# Senior_Project_Board_v2.net
KiCad netlist of a schematic drawn in EAGLE
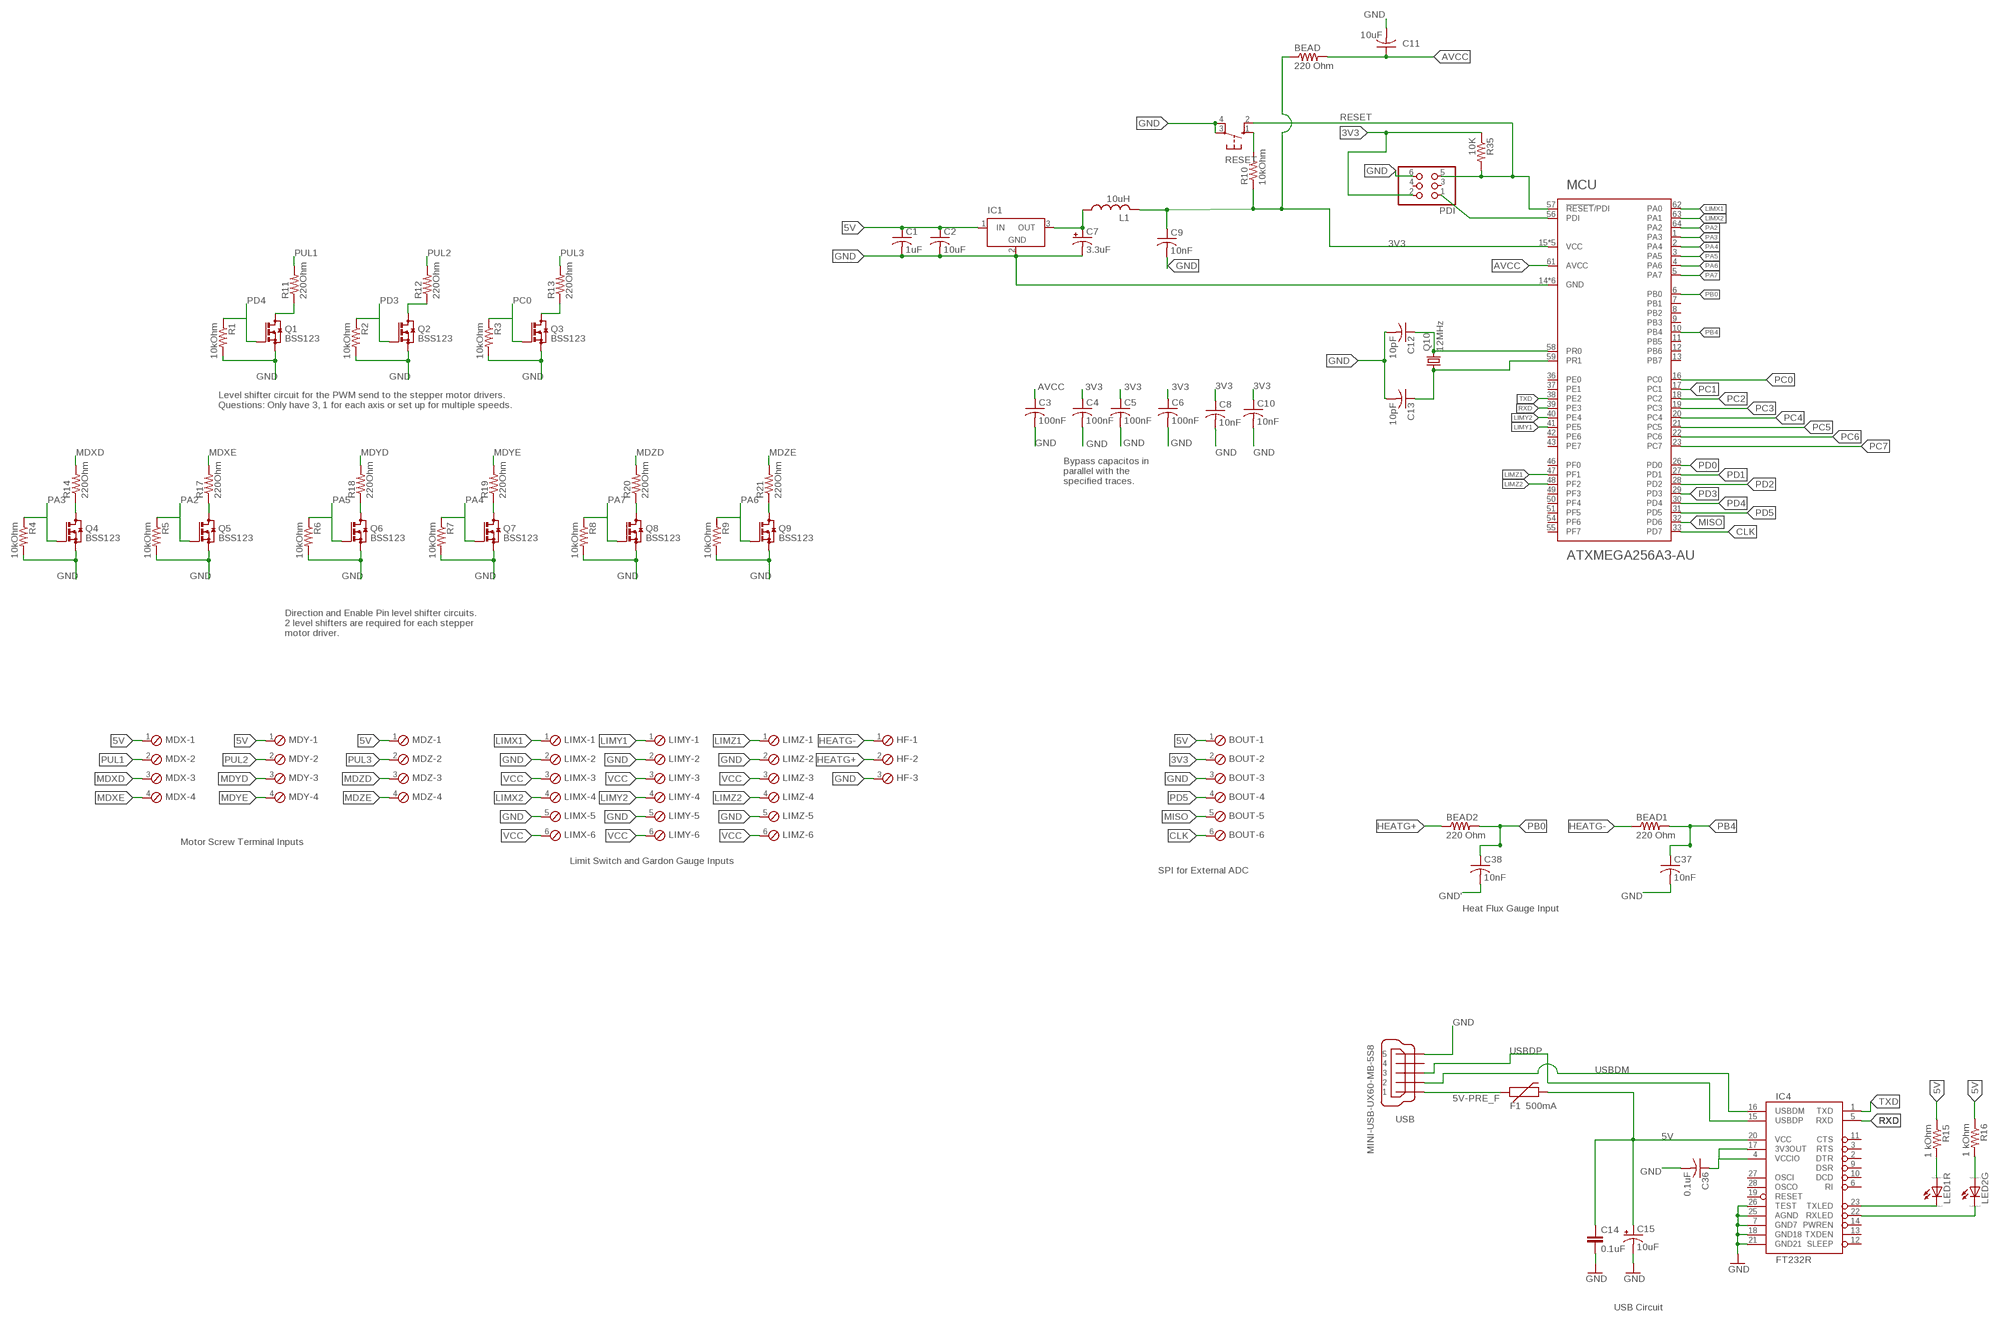
[diagram p0: schematic, sheet 1, part 1 of 3]
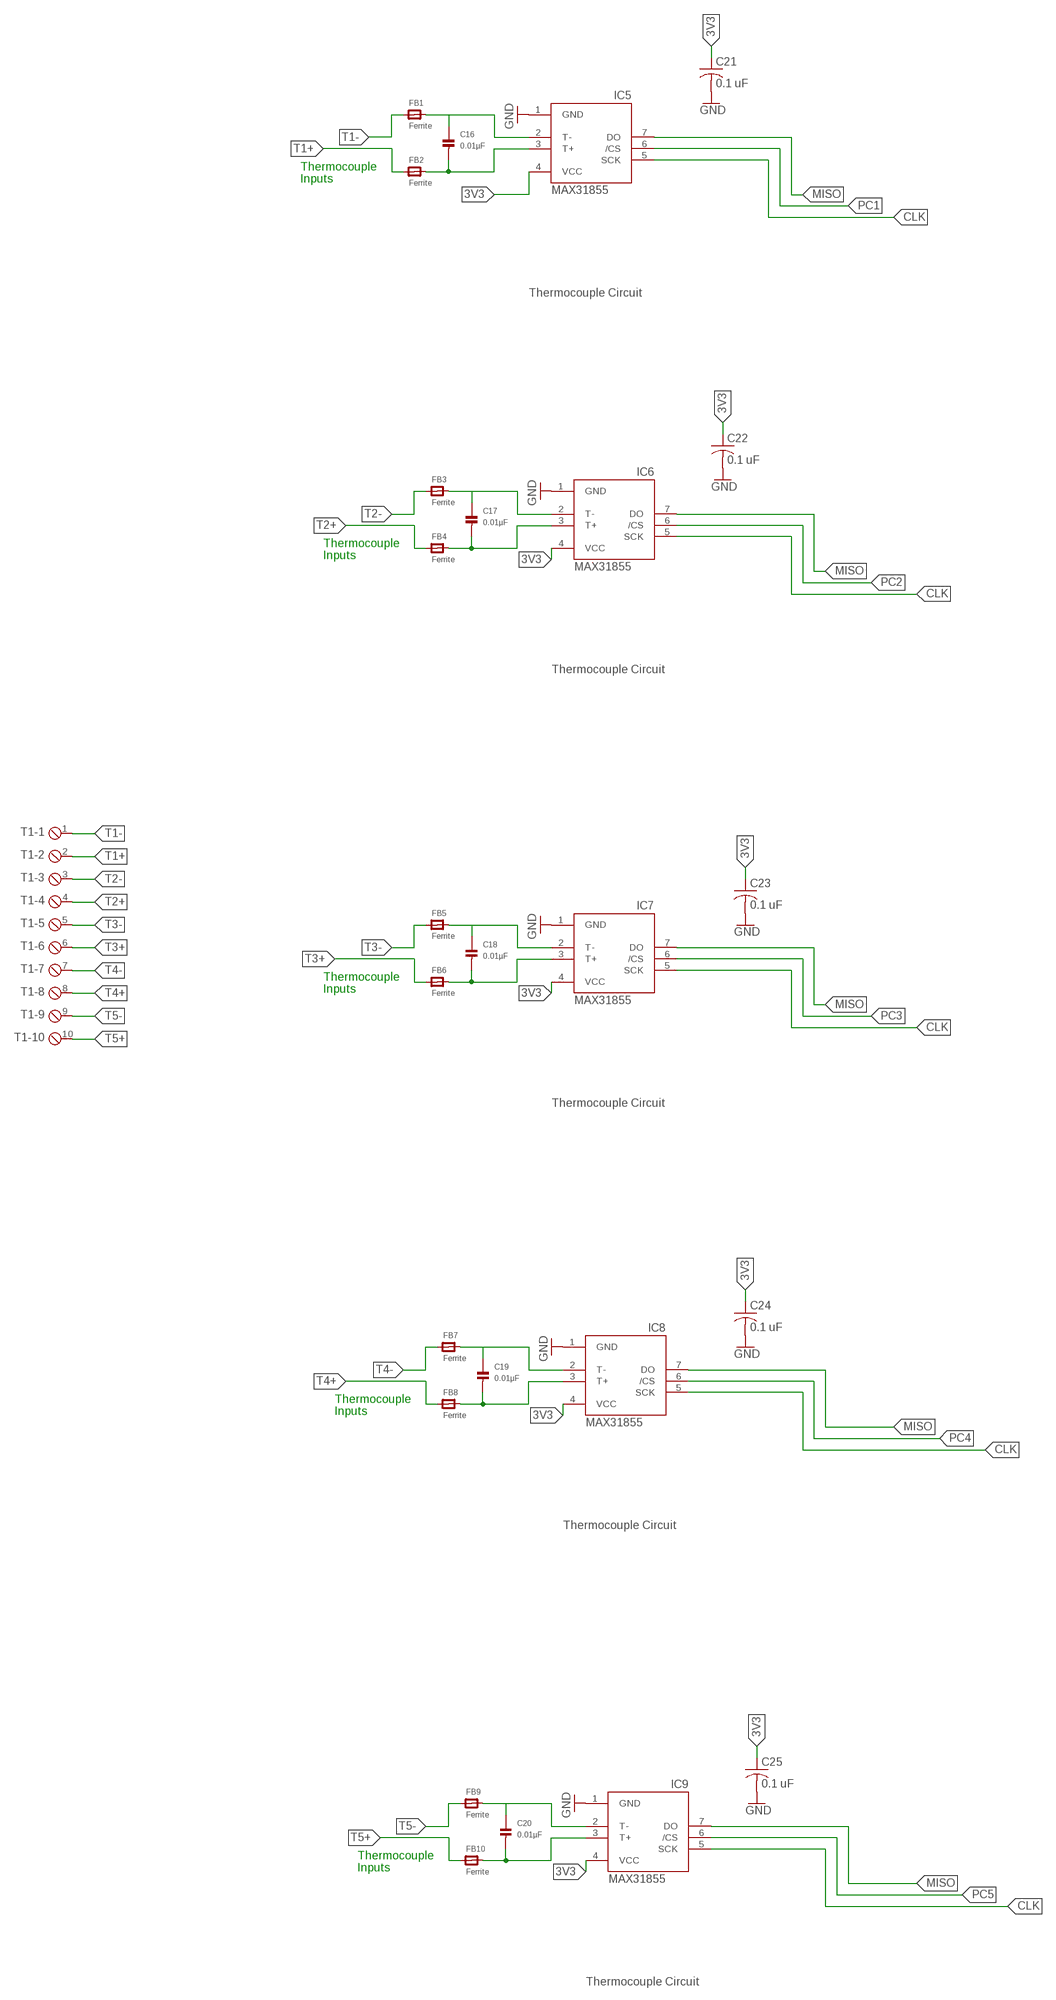
[diagram p1: schematic, sheet 1, part 2 of 3]
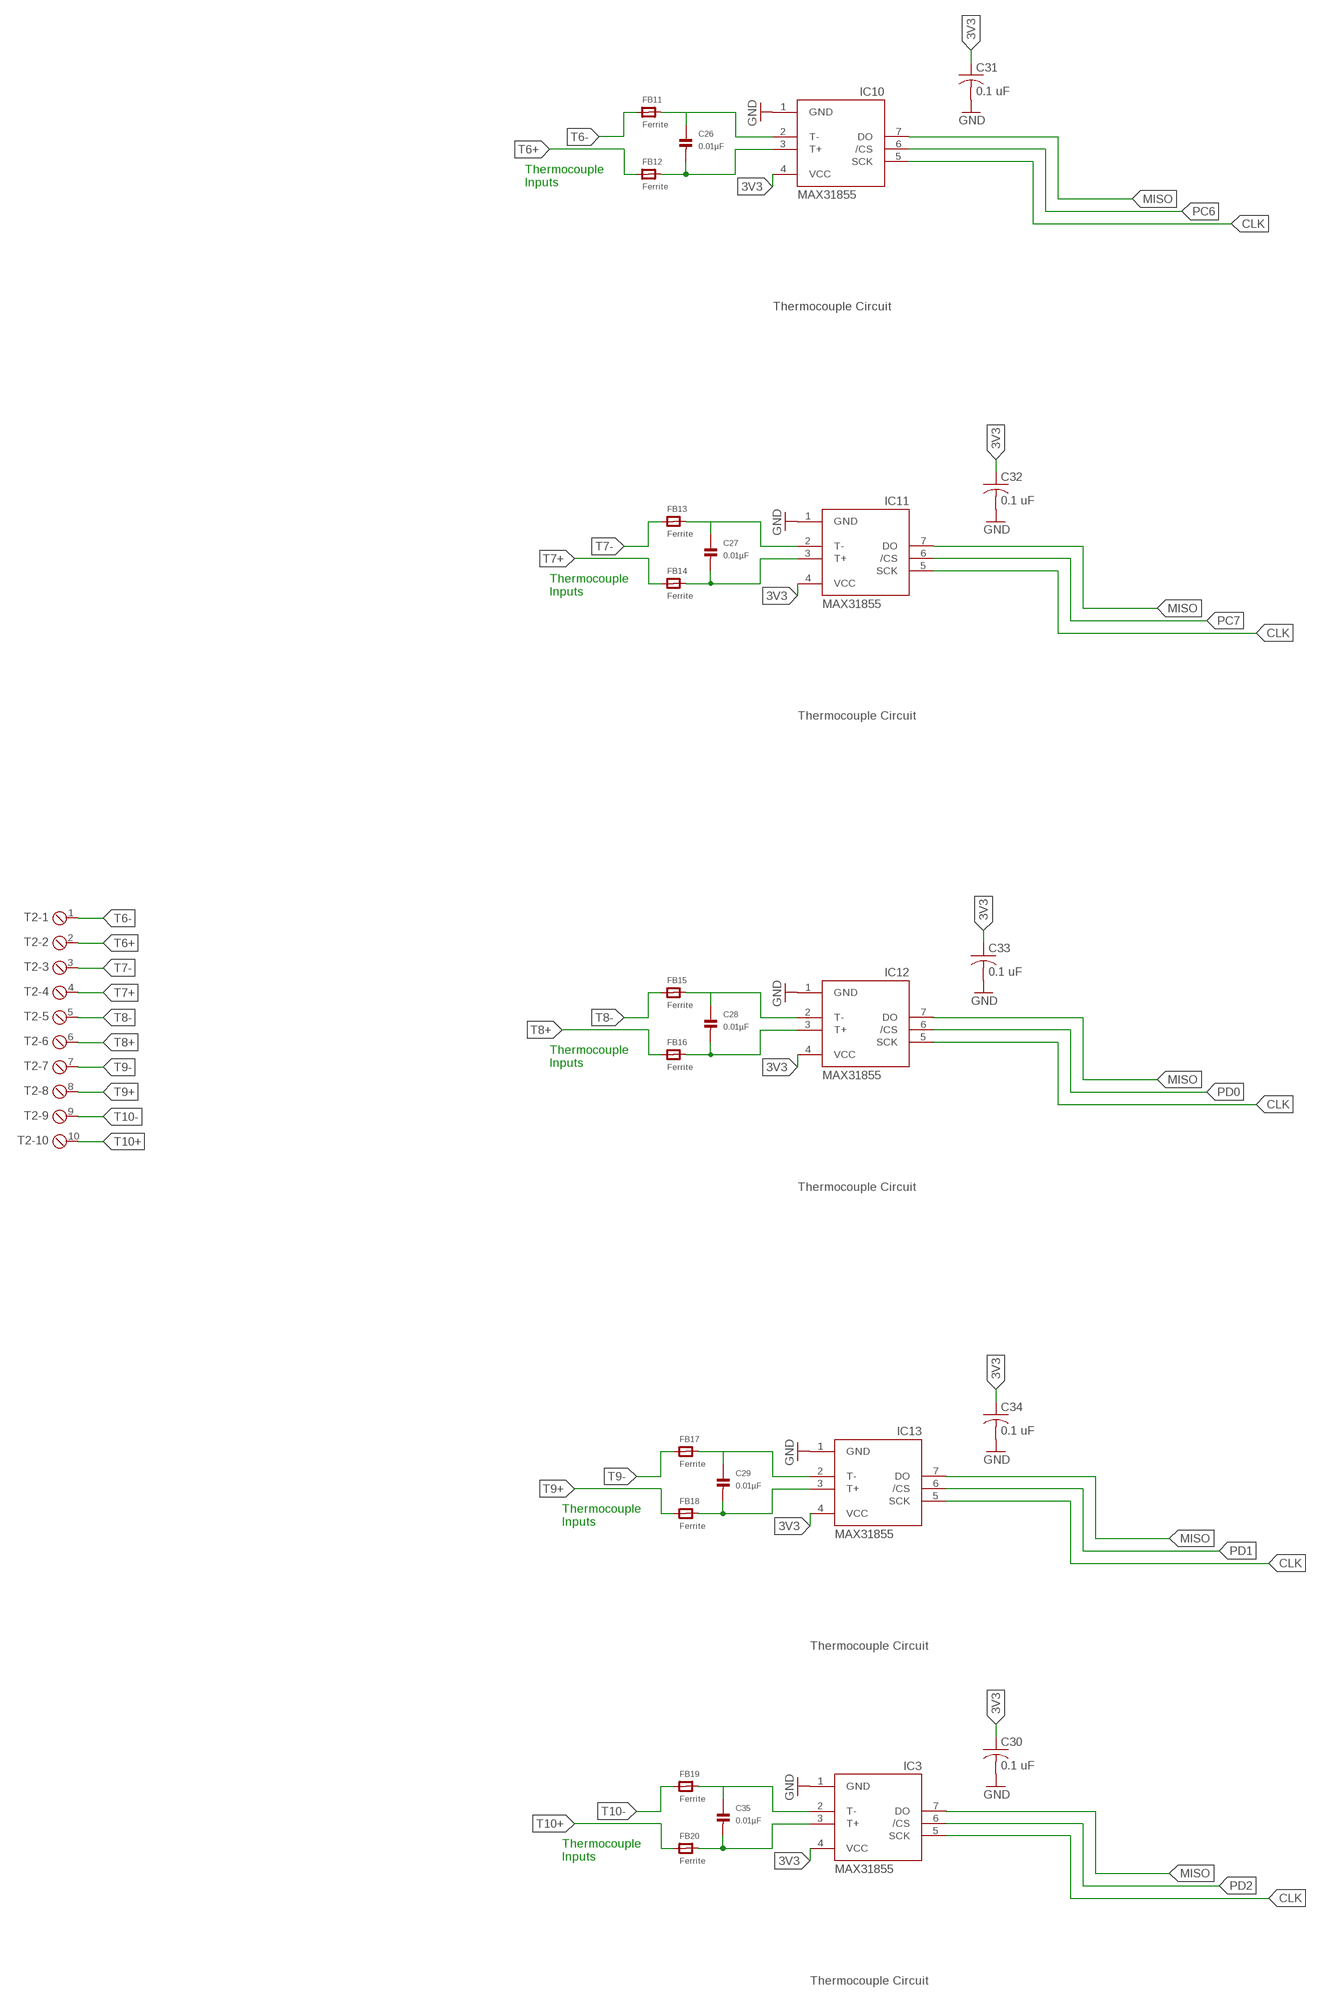
[diagram p2: schematic, sheet 1, part 3 of 3]

(export (version "E")
  (design (tool "Eeschema 10.0.6"))
  (components
    (comp (ref "BEAD")
      (value "220 Ohm")
      (footprint "eagle-import:R0805")
      (libsource (lib "eagle-import") (part "rcl_R-US_R0805"))
    )
    (comp (ref "BEAD1")
      (value "220 Ohm")
      (footprint "eagle-import:R0805")
      (libsource (lib "eagle-import") (part "rcl_R-US_R0805"))
    )
    (comp (ref "BEAD2")
      (value "220 Ohm")
      (footprint "eagle-import:R0805")
      (libsource (lib "eagle-import") (part "rcl_R-US_R0805"))
    )
    (comp (ref "BOUT")
      (value "MPT6")
      (footprint "eagle-import:6POL254")
      (libsource (lib "eagle-import") (part "MPT6"))
    )
    (comp (ref "C1")
      (value "1uF")
      (footprint "eagle-import:C0805")
      (libsource (lib "eagle-import") (part "rcl_C-USC0805"))
    )
    (comp (ref "C2")
      (value "10uF")
      (footprint "eagle-import:C0805")
      (libsource (lib "eagle-import") (part "rcl_C-USC0805"))
    )
    (comp (ref "C3")
      (value "100nF")
      (footprint "eagle-import:C0805")
      (libsource (lib "eagle-import") (part "rcl_C-USC0805"))
    )
    (comp (ref "C4")
      (value "100nF")
      (footprint "eagle-import:C0805")
      (libsource (lib "eagle-import") (part "rcl_C-USC0805"))
    )
    (comp (ref "C5")
      (value "100nF")
      (footprint "eagle-import:C0805")
      (libsource (lib "eagle-import") (part "rcl_C-USC0805"))
    )
    (comp (ref "C6")
      (value "100nF")
      (footprint "eagle-import:C0805")
      (libsource (lib "eagle-import") (part "rcl_C-USC0805"))
    )
    (comp (ref "C7")
      (value "3.3uF")
      (footprint "eagle-import:CT3216")
      (libsource (lib "eagle-import") (part "CPOL-USCT3216"))
    )
    (comp (ref "C8")
      (value "10nF")
      (footprint "eagle-import:C0805")
      (libsource (lib "eagle-import") (part "rcl_C-USC0805"))
    )
    (comp (ref "C9")
      (value "10nF")
      (footprint "eagle-import:C0805")
      (libsource (lib "eagle-import") (part "rcl_C-USC0805"))
    )
    (comp (ref "C10")
      (value "10nF")
      (footprint "eagle-import:C0805")
      (libsource (lib "eagle-import") (part "rcl_C-USC0805"))
    )
    (comp (ref "C11")
      (value "10uF")
      (footprint "eagle-import:C0805")
      (libsource (lib "eagle-import") (part "rcl_C-USC0805"))
    )
    (comp (ref "C12")
      (value "10pF")
      (footprint "eagle-import:C0805")
      (libsource (lib "eagle-import") (part "rcl_C-USC0805"))
    )
    (comp (ref "C13")
      (value "10pF")
      (footprint "eagle-import:C0805")
      (libsource (lib "eagle-import") (part "rcl_C-USC0805"))
    )
    (comp (ref "C14")
      (value "0.1uF")
      (footprint "eagle-import:0603-CAP")
      (libsource (lib "eagle-import") (part "0.1UF-25V(+80/-20%)(0603)"))
    )
    (comp (ref "C15")
      (value "10uF")
      (footprint "eagle-import:EIA3216")
      (libsource (lib "eagle-import") (part "10UF-16V-10%(TANT)"))
    )
    (comp (ref "C16")
      (value "0.01µF")
      (footprint "eagle-import:_0805")
      (libsource (lib "eagle-import") (part "CAP_CERAMIC_0805"))
    )
    (comp (ref "C17")
      (value "0.01µF")
      (footprint "eagle-import:_0805")
      (libsource (lib "eagle-import") (part "CAP_CERAMIC_0805"))
    )
    (comp (ref "C18")
      (value "0.01µF")
      (footprint "eagle-import:_0805")
      (libsource (lib "eagle-import") (part "CAP_CERAMIC_0805"))
    )
    (comp (ref "C19")
      (value "0.01µF")
      (footprint "eagle-import:_0805")
      (libsource (lib "eagle-import") (part "CAP_CERAMIC_0805"))
    )
    (comp (ref "C20")
      (value "0.01µF")
      (footprint "eagle-import:_0805")
      (libsource (lib "eagle-import") (part "CAP_CERAMIC_0805"))
    )
    (comp (ref "C21")
      (value "0.1 uF")
      (footprint "eagle-import:C0805K")
      (libsource (lib "eagle-import") (part "C-USC0805K"))
    )
    (comp (ref "C22")
      (value "0.1 uF")
      (footprint "eagle-import:C0805K")
      (libsource (lib "eagle-import") (part "C-USC0805K"))
    )
    (comp (ref "C23")
      (value "0.1 uF")
      (footprint "eagle-import:C0805K")
      (libsource (lib "eagle-import") (part "C-USC0805K"))
    )
    (comp (ref "C24")
      (value "0.1 uF")
      (footprint "eagle-import:C0805K")
      (libsource (lib "eagle-import") (part "C-USC0805K"))
    )
    (comp (ref "C25")
      (value "0.1 uF")
      (footprint "eagle-import:C0805K")
      (libsource (lib "eagle-import") (part "C-USC0805K"))
    )
    (comp (ref "C26")
      (value "0.01µF")
      (footprint "eagle-import:_0805")
      (libsource (lib "eagle-import") (part "CAP_CERAMIC_0805"))
    )
    (comp (ref "C27")
      (value "0.01µF")
      (footprint "eagle-import:_0805")
      (libsource (lib "eagle-import") (part "CAP_CERAMIC_0805"))
    )
    (comp (ref "C28")
      (value "0.01µF")
      (footprint "eagle-import:_0805")
      (libsource (lib "eagle-import") (part "CAP_CERAMIC_0805"))
    )
    (comp (ref "C29")
      (value "0.01µF")
      (footprint "eagle-import:_0805")
      (libsource (lib "eagle-import") (part "CAP_CERAMIC_0805"))
    )
    (comp (ref "C30")
      (value "0.1 uF")
      (footprint "eagle-import:C0805K")
      (libsource (lib "eagle-import") (part "C-USC0805K"))
    )
    (comp (ref "C31")
      (value "0.1 uF")
      (footprint "eagle-import:C0805K")
      (libsource (lib "eagle-import") (part "C-USC0805K"))
    )
    (comp (ref "C32")
      (value "0.1 uF")
      (footprint "eagle-import:C0805K")
      (libsource (lib "eagle-import") (part "C-USC0805K"))
    )
    (comp (ref "C33")
      (value "0.1 uF")
      (footprint "eagle-import:C0805K")
      (libsource (lib "eagle-import") (part "C-USC0805K"))
    )
    (comp (ref "C34")
      (value "0.1 uF")
      (footprint "eagle-import:C0805K")
      (libsource (lib "eagle-import") (part "C-USC0805K"))
    )
    (comp (ref "C35")
      (value "0.01µF")
      (footprint "eagle-import:_0805")
      (libsource (lib "eagle-import") (part "CAP_CERAMIC_0805"))
    )
    (comp (ref "C36")
      (value "0.1uF")
      (footprint "eagle-import:C0805")
      (libsource (lib "eagle-import") (part "rcl_C-USC0805"))
    )
    (comp (ref "C37")
      (value "10nF")
      (footprint "eagle-import:C0805")
      (libsource (lib "eagle-import") (part "rcl_C-USC0805"))
    )
    (comp (ref "C38")
      (value "10nF")
      (footprint "eagle-import:C0805")
      (libsource (lib "eagle-import") (part "rcl_C-USC0805"))
    )
    (comp (ref "F1")
      (value "500mA")
      (footprint "eagle-import:PTC-1206")
      (libsource (lib "eagle-import") (part "PTCSMD"))
    )
    (comp (ref "FB1")
      (value "Ferrite")
      (footprint "eagle-import:_0805")
      (libsource (lib "eagle-import") (part "FERRITE_0805"))
    )
    (comp (ref "FB2")
      (value "Ferrite")
      (footprint "eagle-import:_0805")
      (libsource (lib "eagle-import") (part "FERRITE_0805"))
    )
    (comp (ref "FB3")
      (value "Ferrite")
      (footprint "eagle-import:_0805")
      (libsource (lib "eagle-import") (part "FERRITE_0805"))
    )
    (comp (ref "FB4")
      (value "Ferrite")
      (footprint "eagle-import:_0805")
      (libsource (lib "eagle-import") (part "FERRITE_0805"))
    )
    (comp (ref "FB5")
      (value "Ferrite")
      (footprint "eagle-import:_0805")
      (libsource (lib "eagle-import") (part "FERRITE_0805"))
    )
    (comp (ref "FB6")
      (value "Ferrite")
      (footprint "eagle-import:_0805")
      (libsource (lib "eagle-import") (part "FERRITE_0805"))
    )
    (comp (ref "FB7")
      (value "Ferrite")
      (footprint "eagle-import:_0805")
      (libsource (lib "eagle-import") (part "FERRITE_0805"))
    )
    (comp (ref "FB8")
      (value "Ferrite")
      (footprint "eagle-import:_0805")
      (libsource (lib "eagle-import") (part "FERRITE_0805"))
    )
    (comp (ref "FB9")
      (value "Ferrite")
      (footprint "eagle-import:_0805")
      (libsource (lib "eagle-import") (part "FERRITE_0805"))
    )
    (comp (ref "FB10")
      (value "Ferrite")
      (footprint "eagle-import:_0805")
      (libsource (lib "eagle-import") (part "FERRITE_0805"))
    )
    (comp (ref "FB11")
      (value "Ferrite")
      (footprint "eagle-import:_0805")
      (libsource (lib "eagle-import") (part "FERRITE_0805"))
    )
    (comp (ref "FB12")
      (value "Ferrite")
      (footprint "eagle-import:_0805")
      (libsource (lib "eagle-import") (part "FERRITE_0805"))
    )
    (comp (ref "FB13")
      (value "Ferrite")
      (footprint "eagle-import:_0805")
      (libsource (lib "eagle-import") (part "FERRITE_0805"))
    )
    (comp (ref "FB14")
      (value "Ferrite")
      (footprint "eagle-import:_0805")
      (libsource (lib "eagle-import") (part "FERRITE_0805"))
    )
    (comp (ref "FB15")
      (value "Ferrite")
      (footprint "eagle-import:_0805")
      (libsource (lib "eagle-import") (part "FERRITE_0805"))
    )
    (comp (ref "FB16")
      (value "Ferrite")
      (footprint "eagle-import:_0805")
      (libsource (lib "eagle-import") (part "FERRITE_0805"))
    )
    (comp (ref "FB17")
      (value "Ferrite")
      (footprint "eagle-import:_0805")
      (libsource (lib "eagle-import") (part "FERRITE_0805"))
    )
    (comp (ref "FB18")
      (value "Ferrite")
      (footprint "eagle-import:_0805")
      (libsource (lib "eagle-import") (part "FERRITE_0805"))
    )
    (comp (ref "FB19")
      (value "Ferrite")
      (footprint "eagle-import:_0805")
      (libsource (lib "eagle-import") (part "FERRITE_0805"))
    )
    (comp (ref "FB20")
      (value "Ferrite")
      (footprint "eagle-import:_0805")
      (libsource (lib "eagle-import") (part "FERRITE_0805"))
    )
    (comp (ref "HF")
      (value "MPT3")
      (footprint "eagle-import:3POL254")
      (libsource (lib "eagle-import") (part "MPT3"))
    )
    (comp (ref "IC1")
      (value "LT1129CST5")
      (footprint "eagle-import:SOT223")
      (fields (field (name "MPN") "LT1129CST-5#PBF"))
      (libsource (lib "eagle-import") (part "LT1129CST5"))
    )
    (comp (ref "IC3")
      (value "MAX31855")
      (footprint "eagle-import:SO08")
      (libsource (lib "eagle-import") (part "MAX6675"))
    )
    (comp (ref "IC4")
      (value "FT232R")
      (footprint "eagle-import:SSOP28DB")
      (libsource (lib "eagle-import") (part "FT232RLSSOP"))
    )
    (comp (ref "IC5")
      (value "MAX31855")
      (footprint "eagle-import:SO08")
      (libsource (lib "eagle-import") (part "MAX6675"))
    )
    (comp (ref "IC6")
      (value "MAX31855")
      (footprint "eagle-import:SO08")
      (libsource (lib "eagle-import") (part "MAX6675"))
    )
    (comp (ref "IC7")
      (value "MAX31855")
      (footprint "eagle-import:SO08")
      (libsource (lib "eagle-import") (part "MAX6675"))
    )
    (comp (ref "IC8")
      (value "MAX31855")
      (footprint "eagle-import:SO08")
      (libsource (lib "eagle-import") (part "MAX6675"))
    )
    (comp (ref "IC9")
      (value "MAX31855")
      (footprint "eagle-import:SO08")
      (libsource (lib "eagle-import") (part "MAX6675"))
    )
    (comp (ref "IC10")
      (value "MAX31855")
      (footprint "eagle-import:SO08")
      (libsource (lib "eagle-import") (part "MAX6675"))
    )
    (comp (ref "IC11")
      (value "MAX31855")
      (footprint "eagle-import:SO08")
      (libsource (lib "eagle-import") (part "MAX6675"))
    )
    (comp (ref "IC12")
      (value "MAX31855")
      (footprint "eagle-import:SO08")
      (libsource (lib "eagle-import") (part "MAX6675"))
    )
    (comp (ref "IC13")
      (value "MAX31855")
      (footprint "eagle-import:SO08")
      (libsource (lib "eagle-import") (part "MAX6675"))
    )
    (comp (ref "L1")
      (value "10uH")
      (footprint "eagle-import:L1812")
      (libsource (lib "eagle-import") (part "L-USL1812"))
    )
    (comp (ref "LED1R")
      (value "LED_E")
      (footprint "eagle-import:LED_1206")
      (libsource (lib "eagle-import") (part "LED_E"))
    )
    (comp (ref "LED2G")
      (value "LED_E")
      (footprint "eagle-import:LED_1206")
      (libsource (lib "eagle-import") (part "LED_E"))
    )
    (comp (ref "LIMX")
      (value "MPT6")
      (footprint "eagle-import:6POL254")
      (libsource (lib "eagle-import") (part "MPT6"))
    )
    (comp (ref "LIMY")
      (value "MPT6")
      (footprint "eagle-import:6POL254")
      (libsource (lib "eagle-import") (part "MPT6"))
    )
    (comp (ref "LIMZ")
      (value "MPT6")
      (footprint "eagle-import:6POL254")
      (libsource (lib "eagle-import") (part "MPT6"))
    )
    (comp (ref "MCU")
      (value "ATXMEGA256A3-AU")
      (footprint "eagle-import:TQFP-64A-64")
      (libsource (lib "eagle-import") (part "ATXMEGA256A3-AU"))
    )
    (comp (ref "MDX")
      (value "MPT4")
      (footprint "eagle-import:4POL254")
      (libsource (lib "eagle-import") (part "MPT4"))
    )
    (comp (ref "MDY")
      (value "MPT4")
      (footprint "eagle-import:4POL254")
      (libsource (lib "eagle-import") (part "MPT4"))
    )
    (comp (ref "MDZ")
      (value "MPT4")
      (footprint "eagle-import:4POL254")
      (libsource (lib "eagle-import") (part "MPT4"))
    )
    (comp (ref "PDI")
      (value "PINHD-2X3")
      (footprint "eagle-import:2X03")
      (libsource (lib "eagle-import") (part "PINHD-2X3"))
    )
    (comp (ref "Q1")
      (value "BSS123")
      (footprint "eagle-import:SOT23")
      (libsource (lib "eagle-import") (part "BSS123"))
    )
    (comp (ref "Q2")
      (value "BSS123")
      (footprint "eagle-import:SOT23")
      (libsource (lib "eagle-import") (part "BSS123"))
    )
    (comp (ref "Q3")
      (value "BSS123")
      (footprint "eagle-import:SOT23")
      (libsource (lib "eagle-import") (part "BSS123"))
    )
    (comp (ref "Q4")
      (value "BSS123")
      (footprint "eagle-import:SOT23")
      (libsource (lib "eagle-import") (part "BSS123"))
    )
    (comp (ref "Q5")
      (value "BSS123")
      (footprint "eagle-import:SOT23")
      (libsource (lib "eagle-import") (part "BSS123"))
    )
    (comp (ref "Q6")
      (value "BSS123")
      (footprint "eagle-import:SOT23")
      (libsource (lib "eagle-import") (part "BSS123"))
    )
    (comp (ref "Q7")
      (value "BSS123")
      (footprint "eagle-import:SOT23")
      (libsource (lib "eagle-import") (part "BSS123"))
    )
    (comp (ref "Q8")
      (value "BSS123")
      (footprint "eagle-import:SOT23")
      (libsource (lib "eagle-import") (part "BSS123"))
    )
    (comp (ref "Q9")
      (value "BSS123")
      (footprint "eagle-import:SOT23")
      (libsource (lib "eagle-import") (part "BSS123"))
    )
    (comp (ref "Q10")
      (value "12MHz")
      (footprint "eagle-import:HC49_S")
      (libsource (lib "eagle-import") (part "CRYSTALHC49S"))
    )
    (comp (ref "R1")
      (value "10kOhm")
      (footprint "eagle-import:R0805")
      (libsource (lib "eagle-import") (part "rcl_R-US_R0805"))
    )
    (comp (ref "R2")
      (value "10kOhm")
      (footprint "eagle-import:R0805")
      (libsource (lib "eagle-import") (part "rcl_R-US_R0805"))
    )
    (comp (ref "R3")
      (value "10kOhm")
      (footprint "eagle-import:R0805")
      (libsource (lib "eagle-import") (part "rcl_R-US_R0805"))
    )
    (comp (ref "R4")
      (value "10kOhm")
      (footprint "eagle-import:R0805")
      (libsource (lib "eagle-import") (part "rcl_R-US_R0805"))
    )
    (comp (ref "R5")
      (value "10kOhm")
      (footprint "eagle-import:R0805")
      (libsource (lib "eagle-import") (part "rcl_R-US_R0805"))
    )
    (comp (ref "R6")
      (value "10kOhm")
      (footprint "eagle-import:R0805")
      (libsource (lib "eagle-import") (part "rcl_R-US_R0805"))
    )
    (comp (ref "R7")
      (value "10kOhm")
      (footprint "eagle-import:R0805")
      (libsource (lib "eagle-import") (part "rcl_R-US_R0805"))
    )
    (comp (ref "R8")
      (value "10kOhm")
      (footprint "eagle-import:R0805")
      (libsource (lib "eagle-import") (part "rcl_R-US_R0805"))
    )
    (comp (ref "R9")
      (value "10kOhm")
      (footprint "eagle-import:R0805")
      (libsource (lib "eagle-import") (part "rcl_R-US_R0805"))
    )
    (comp (ref "R10")
      (value "10kOhm")
      (footprint "eagle-import:R0805")
      (libsource (lib "eagle-import") (part "rcl_R-US_R0805"))
    )
    (comp (ref "R11")
      (value "220Ohm")
      (footprint "eagle-import:R0805")
      (libsource (lib "eagle-import") (part "rcl_R-US_R0805"))
    )
    (comp (ref "R12")
      (value "220Ohm")
      (footprint "eagle-import:R0805")
      (libsource (lib "eagle-import") (part "rcl_R-US_R0805"))
    )
    (comp (ref "R13")
      (value "220Ohm")
      (footprint "eagle-import:R0805")
      (libsource (lib "eagle-import") (part "rcl_R-US_R0805"))
    )
    (comp (ref "R14")
      (value "220Ohm")
      (footprint "eagle-import:R0805")
      (libsource (lib "eagle-import") (part "rcl_R-US_R0805"))
    )
    (comp (ref "R15")
      (value "1 kOhm")
      (footprint "eagle-import:R0805")
      (libsource (lib "eagle-import") (part "rcl_R-US_R0805"))
    )
    (comp (ref "R16")
      (value "1 kOhm")
      (footprint "eagle-import:R0805")
      (libsource (lib "eagle-import") (part "rcl_R-US_R0805"))
    )
    (comp (ref "R17")
      (value "220Ohm")
      (footprint "eagle-import:R0805")
      (libsource (lib "eagle-import") (part "rcl_R-US_R0805"))
    )
    (comp (ref "R18")
      (value "220Ohm")
      (footprint "eagle-import:R0805")
      (libsource (lib "eagle-import") (part "rcl_R-US_R0805"))
    )
    (comp (ref "R19")
      (value "220Ohm")
      (footprint "eagle-import:R0805")
      (libsource (lib "eagle-import") (part "rcl_R-US_R0805"))
    )
    (comp (ref "R20")
      (value "220Ohm")
      (footprint "eagle-import:R0805")
      (libsource (lib "eagle-import") (part "rcl_R-US_R0805"))
    )
    (comp (ref "R21")
      (value "220Ohm")
      (footprint "eagle-import:R0805")
      (libsource (lib "eagle-import") (part "rcl_R-US_R0805"))
    )
    (comp (ref "R35")
      (value "10K")
      (footprint "eagle-import:R0805")
      (libsource (lib "eagle-import") (part "R-US_R0805"))
    )
    (comp (ref "RESET")
      (value "10-XX")
      (footprint "eagle-import:B3F-10XX")
      (fields (field (name "MPN") "B3F-1000"))
      (libsource (lib "eagle-import") (part "10-XX"))
    )
    (comp (ref "T1")
      (value "MPT10")
      (footprint "eagle-import:10POL254")
      (libsource (lib "eagle-import") (part "MPT10"))
    )
    (comp (ref "T2")
      (value "MPT10")
      (footprint "eagle-import:10POL254")
      (libsource (lib "eagle-import") (part "MPT10"))
    )
    (comp (ref "USB")
      (value "MINI-USB-UX60-MB-5S8")
      (footprint "eagle-import:UX60-MB-5S8")
      (libsource (lib "eagle-import") (part "MINI-USB-UX60-MB-5S8"))
    )
  )
  (nets
    (net (code "1") (name "/5V-PRE_F") (class "Default")
      (node (ref "F1") (pin "1") (pinfunction "1_1") (pintype "bidirectional"))
      (node (ref "USB") (pin "1") (pinfunction "1_1") (pintype "input"))
    )
    (net (code "2") (name "/GND'") (class "Default")
      (node (ref "C38") (pin "2") (pinfunction "2_2") (pintype "passive"))
    )
    (net (code "3") (name "/RESET") (class "Default")
      (node (ref "MCU") (pin "57") (pinfunction "~{RESET}/PDI_57") (pintype "bidirectional"))
      (node (ref "PDI") (pin "5") (pinfunction "5_5") (pintype "passive"))
      (node (ref "R35") (pin "2") (pinfunction "2_2") (pintype "passive"))
      (node (ref "RESET") (pin "2") (pinfunction "S1_2") (pintype "passive"))
    )
    (net (code "4") (name "/USBDM") (class "Default")
      (node (ref "IC4") (pin "16") (pinfunction "USBDM_16") (pintype "bidirectional"))
      (node (ref "USB") (pin "2") (pinfunction "2_2") (pintype "input"))
    )
    (net (code "5") (name "/USBDP") (class "Default")
      (node (ref "IC4") (pin "15") (pinfunction "USBDP_15") (pintype "bidirectional"))
      (node (ref "USB") (pin "3") (pinfunction "3_3") (pintype "input"))
    )
    (net (code "6") (name "3V3") (class "Default")
      (node (ref "BEAD") (pin "1") (pinfunction "1_1") (pintype "passive"))
      (node (ref "BOUT") (pin "2") (pinfunction "1_2") (pintype "passive"))
      (node (ref "C10") (pin "1") (pinfunction "1_1") (pintype "passive"))
      (node (ref "C21") (pin "1") (pinfunction "1_1") (pintype "passive"))
      (node (ref "C22") (pin "1") (pinfunction "1_1") (pintype "passive"))
      (node (ref "C23") (pin "1") (pinfunction "1_1") (pintype "passive"))
      (node (ref "C24") (pin "1") (pinfunction "1_1") (pintype "passive"))
      (node (ref "C25") (pin "1") (pinfunction "1_1") (pintype "passive"))
      (node (ref "C30") (pin "1") (pinfunction "1_1") (pintype "passive"))
      (node (ref "C31") (pin "1") (pinfunction "1_1") (pintype "passive"))
      (node (ref "C32") (pin "1") (pinfunction "1_1") (pintype "passive"))
      (node (ref "C33") (pin "1") (pinfunction "1_1") (pintype "passive"))
      (node (ref "C34") (pin "1") (pinfunction "1_1") (pintype "passive"))
      (node (ref "C4") (pin "1") (pinfunction "1_1") (pintype "passive"))
      (node (ref "C5") (pin "1") (pinfunction "1_1") (pintype "passive"))
      (node (ref "C6") (pin "1") (pinfunction "1_1") (pintype "passive"))
      (node (ref "C8") (pin "1") (pinfunction "1_1") (pintype "passive"))
      (node (ref "C9") (pin "1") (pinfunction "1_1") (pintype "passive"))
      (node (ref "IC10") (pin "4") (pinfunction "VCC_4") (pintype "power_in"))
      (node (ref "IC11") (pin "4") (pinfunction "VCC_4") (pintype "power_in"))
      (node (ref "IC12") (pin "4") (pinfunction "VCC_4") (pintype "power_in"))
      (node (ref "IC13") (pin "4") (pinfunction "VCC_4") (pintype "power_in"))
      (node (ref "IC3") (pin "4") (pinfunction "VCC_4") (pintype "power_in"))
      (node (ref "IC5") (pin "4") (pinfunction "VCC_4") (pintype "power_in"))
      (node (ref "IC6") (pin "4") (pinfunction "VCC_4") (pintype "power_in"))
      (node (ref "IC7") (pin "4") (pinfunction "VCC_4") (pintype "power_in"))
      (node (ref "IC8") (pin "4") (pinfunction "VCC_4") (pintype "power_in"))
      (node (ref "IC9") (pin "4") (pinfunction "VCC_4") (pintype "power_in"))
      (node (ref "L1") (pin "2") (pinfunction "2_2") (pintype "passive"))
      (node (ref "MCU") (pin "15") (pinfunction "VCC_15") (pintype "power_in"))
      (node (ref "MCU") (pin "25") (pinfunction "VCC_25") (pintype "power_in"))
      (node (ref "MCU") (pin "35") (pinfunction "VCC_35") (pintype "power_in"))
      (node (ref "MCU") (pin "45") (pinfunction "VCC_45") (pintype "power_in"))
      (node (ref "MCU") (pin "53") (pinfunction "VCC_53") (pintype "power_in"))
      (node (ref "PDI") (pin "2") (pinfunction "2_2") (pintype "passive"))
      (node (ref "R10") (pin "1") (pinfunction "1_1") (pintype "passive"))
      (node (ref "R35") (pin "1") (pinfunction "1_1") (pintype "passive"))
    )
    (net (code "7") (name "5V") (class "Default")
      (node (ref "BOUT") (pin "1") (pinfunction "1_1") (pintype "passive"))
      (node (ref "C1") (pin "1") (pinfunction "1_1") (pintype "passive"))
      (node (ref "C14") (pin "1") (pinfunction "1_1") (pintype "passive"))
      (node (ref "C15") (pin "A") (pinfunction "+_A") (pintype "passive"))
      (node (ref "C2") (pin "1") (pinfunction "1_1") (pintype "passive"))
      (node (ref "F1") (pin "2") (pinfunction "2_2") (pintype "bidirectional"))
      (node (ref "IC1") (pin "1") (pinfunction "IN_1") (pintype "input"))
      (node (ref "IC4") (pin "20") (pinfunction "VCC_20") (pintype "power_in"))
      (node (ref "MDX") (pin "1") (pinfunction "1_1") (pintype "passive"))
      (node (ref "MDY") (pin "1") (pinfunction "1_1") (pintype "passive"))
      (node (ref "MDZ") (pin "1") (pinfunction "1_1") (pintype "passive"))
      (node (ref "R15") (pin "1") (pinfunction "1_1") (pintype "passive"))
      (node (ref "R16") (pin "1") (pinfunction "1_1") (pintype "passive"))
    )
    (net (code "8") (name "AVCC") (class "Default")
      (node (ref "BEAD") (pin "2") (pinfunction "2_2") (pintype "passive"))
      (node (ref "C11") (pin "1") (pinfunction "1_1") (pintype "passive"))
      (node (ref "C3") (pin "1") (pinfunction "1_1") (pintype "passive"))
      (node (ref "MCU") (pin "61") (pinfunction "AVCC_61") (pintype "power_in"))
    )
    (net (code "9") (name "CLK") (class "Default")
      (node (ref "BOUT") (pin "6") (pinfunction "1_6") (pintype "passive"))
      (node (ref "IC10") (pin "5") (pinfunction "SCK_5") (pintype "input"))
      (node (ref "IC11") (pin "5") (pinfunction "SCK_5") (pintype "input"))
      (node (ref "IC12") (pin "5") (pinfunction "SCK_5") (pintype "input"))
      (node (ref "IC13") (pin "5") (pinfunction "SCK_5") (pintype "input"))
      (node (ref "IC3") (pin "5") (pinfunction "SCK_5") (pintype "input"))
      (node (ref "IC5") (pin "5") (pinfunction "SCK_5") (pintype "input"))
      (node (ref "IC6") (pin "5") (pinfunction "SCK_5") (pintype "input"))
      (node (ref "IC7") (pin "5") (pinfunction "SCK_5") (pintype "input"))
      (node (ref "IC8") (pin "5") (pinfunction "SCK_5") (pintype "input"))
      (node (ref "IC9") (pin "5") (pinfunction "SCK_5") (pintype "input"))
      (node (ref "MCU") (pin "33") (pinfunction "PD7_33") (pintype "bidirectional"))
    )
    (net (code "10") (name "GND") (class "Default")
      (node (ref "BOUT") (pin "3") (pinfunction "1_3") (pintype "passive"))
      (node (ref "C1") (pin "2") (pinfunction "2_2") (pintype "passive"))
      (node (ref "C10") (pin "2") (pinfunction "2_2") (pintype "passive"))
      (node (ref "C11") (pin "2") (pinfunction "2_2") (pintype "passive"))
      (node (ref "C12") (pin "2") (pinfunction "2_2") (pintype "passive"))
      (node (ref "C13") (pin "2") (pinfunction "2_2") (pintype "passive"))
      (node (ref "C14") (pin "2") (pinfunction "2_2") (pintype "passive"))
      (node (ref "C15") (pin "C") (pinfunction "-_C") (pintype "passive"))
      (node (ref "C2") (pin "2") (pinfunction "2_2") (pintype "passive"))
      (node (ref "C21") (pin "2") (pinfunction "2_2") (pintype "passive"))
      (node (ref "C22") (pin "2") (pinfunction "2_2") (pintype "passive"))
      (node (ref "C23") (pin "2") (pinfunction "2_2") (pintype "passive"))
      (node (ref "C24") (pin "2") (pinfunction "2_2") (pintype "passive"))
      (node (ref "C25") (pin "2") (pinfunction "2_2") (pintype "passive"))
      (node (ref "C3") (pin "2") (pinfunction "2_2") (pintype "passive"))
      (node (ref "C30") (pin "2") (pinfunction "2_2") (pintype "passive"))
      (node (ref "C31") (pin "2") (pinfunction "2_2") (pintype "passive"))
      (node (ref "C32") (pin "2") (pinfunction "2_2") (pintype "passive"))
      (node (ref "C33") (pin "2") (pinfunction "2_2") (pintype "passive"))
      (node (ref "C34") (pin "2") (pinfunction "2_2") (pintype "passive"))
      (node (ref "C36") (pin "2") (pinfunction "2_2") (pintype "passive"))
      (node (ref "C37") (pin "2") (pinfunction "2_2") (pintype "passive"))
      (node (ref "C4") (pin "2") (pinfunction "2_2") (pintype "passive"))
      (node (ref "C5") (pin "2") (pinfunction "2_2") (pintype "passive"))
      (node (ref "C6") (pin "2") (pinfunction "2_2") (pintype "passive"))
      (node (ref "C7") (pin "-") (pinfunction "-_-") (pintype "passive"))
      (node (ref "C8") (pin "2") (pinfunction "2_2") (pintype "passive"))
      (node (ref "C9") (pin "2") (pinfunction "2_2") (pintype "passive"))
      (node (ref "HF") (pin "3") (pinfunction "1_3") (pintype "passive"))
      (node (ref "IC1") (pin "2") (pinfunction "GND_2") (pintype "power_in"))
      (node (ref "IC10") (pin "1") (pinfunction "GND_1") (pintype "power_in"))
      (node (ref "IC11") (pin "1") (pinfunction "GND_1") (pintype "power_in"))
      (node (ref "IC12") (pin "1") (pinfunction "GND_1") (pintype "power_in"))
      (node (ref "IC13") (pin "1") (pinfunction "GND_1") (pintype "power_in"))
      (node (ref "IC3") (pin "1") (pinfunction "GND_1") (pintype "power_in"))
      (node (ref "IC4") (pin "18") (pinfunction "GND18_18") (pintype "power_in"))
      (node (ref "IC4") (pin "21") (pinfunction "GND21_21") (pintype "power_in"))
      (node (ref "IC4") (pin "25") (pinfunction "AGND_25") (pintype "power_in"))
      (node (ref "IC4") (pin "26") (pinfunction "TEST_26") (pintype "input"))
      (node (ref "IC4") (pin "7") (pinfunction "GND7_7") (pintype "power_in"))
      (node (ref "IC5") (pin "1") (pinfunction "GND_1") (pintype "power_in"))
      (node (ref "IC6") (pin "1") (pinfunction "GND_1") (pintype "power_in"))
      (node (ref "IC7") (pin "1") (pinfunction "GND_1") (pintype "power_in"))
      (node (ref "IC8") (pin "1") (pinfunction "GND_1") (pintype "power_in"))
      (node (ref "IC9") (pin "1") (pinfunction "GND_1") (pintype "power_in"))
      (node (ref "LIMX") (pin "2") (pinfunction "1_2") (pintype "passive"))
      (node (ref "LIMX") (pin "5") (pinfunction "1_5") (pintype "passive"))
      (node (ref "LIMY") (pin "2") (pinfunction "1_2") (pintype "passive"))
      (node (ref "LIMY") (pin "5") (pinfunction "1_5") (pintype "passive"))
      (node (ref "LIMZ") (pin "2") (pinfunction "1_2") (pintype "passive"))
      (node (ref "LIMZ") (pin "5") (pinfunction "1_5") (pintype "passive"))
      (node (ref "MCU") (pin "14") (pinfunction "GND_14") (pintype "power_in"))
      (node (ref "MCU") (pin "24") (pinfunction "GND_24") (pintype "power_in"))
      (node (ref "MCU") (pin "34") (pinfunction "GND_34") (pintype "power_in"))
      (node (ref "MCU") (pin "44") (pinfunction "GND_44") (pintype "power_in"))
      (node (ref "MCU") (pin "52") (pinfunction "GND_52") (pintype "power_in"))
      (node (ref "MCU") (pin "60") (pinfunction "GND_60") (pintype "power_in"))
      (node (ref "PDI") (pin "6") (pinfunction "6_6") (pintype "passive"))
      (node (ref "Q1") (pin "2") (pinfunction "S_2") (pintype "passive"))
      (node (ref "Q2") (pin "2") (pinfunction "S_2") (pintype "passive"))
      (node (ref "Q3") (pin "2") (pinfunction "S_2") (pintype "passive"))
      (node (ref "Q4") (pin "2") (pinfunction "S_2") (pintype "passive"))
      (node (ref "Q5") (pin "2") (pinfunction "S_2") (pintype "passive"))
      (node (ref "Q6") (pin "2") (pinfunction "S_2") (pintype "passive"))
      (node (ref "Q7") (pin "2") (pinfunction "S_2") (pintype "passive"))
      (node (ref "Q8") (pin "2") (pinfunction "S_2") (pintype "passive"))
      (node (ref "Q9") (pin "2") (pinfunction "S_2") (pintype "passive"))
      (node (ref "R1") (pin "2") (pinfunction "2_2") (pintype "passive"))
      (node (ref "R2") (pin "2") (pinfunction "2_2") (pintype "passive"))
      (node (ref "R3") (pin "2") (pinfunction "2_2") (pintype "passive"))
      (node (ref "R4") (pin "2") (pinfunction "2_2") (pintype "passive"))
      (node (ref "R5") (pin "2") (pinfunction "2_2") (pintype "passive"))
      (node (ref "R6") (pin "2") (pinfunction "2_2") (pintype "passive"))
      (node (ref "R7") (pin "2") (pinfunction "2_2") (pintype "passive"))
      (node (ref "R8") (pin "2") (pinfunction "2_2") (pintype "passive"))
      (node (ref "R9") (pin "2") (pinfunction "2_2") (pintype "passive"))
      (node (ref "RESET") (pin "3") (pinfunction "P_3") (pintype "passive"))
      (node (ref "RESET") (pin "4") (pinfunction "P1_4") (pintype "passive"))
      (node (ref "USB") (pin "5") (pinfunction "5_5") (pintype "input"))
    )
    (net (code "11") (name "HEATG+") (class "Default")
      (node (ref "BEAD2") (pin "1") (pinfunction "1_1") (pintype "passive"))
      (node (ref "HF") (pin "2") (pinfunction "1_2") (pintype "passive"))
    )
    (net (code "12") (name "HEATG-") (class "Default")
      (node (ref "BEAD1") (pin "1") (pinfunction "1_1") (pintype "passive"))
      (node (ref "HF") (pin "1") (pinfunction "1_1") (pintype "passive"))
    )
    (net (code "13") (name "LIMX1") (class "Default")
      (node (ref "LIMX") (pin "1") (pinfunction "1_1") (pintype "passive"))
      (node (ref "MCU") (pin "62") (pinfunction "PA0_62") (pintype "bidirectional"))
    )
    (net (code "14") (name "LIMX2") (class "Default")
      (node (ref "LIMX") (pin "4") (pinfunction "1_4") (pintype "passive"))
      (node (ref "MCU") (pin "63") (pinfunction "PA1_63") (pintype "bidirectional"))
    )
    (net (code "15") (name "LIMY1") (class "Default")
      (node (ref "LIMY") (pin "1") (pinfunction "1_1") (pintype "passive"))
      (node (ref "MCU") (pin "41") (pinfunction "PE5_41") (pintype "bidirectional"))
    )
    (net (code "16") (name "LIMY2") (class "Default")
      (node (ref "LIMY") (pin "4") (pinfunction "1_4") (pintype "passive"))
      (node (ref "MCU") (pin "40") (pinfunction "PE4_40") (pintype "bidirectional"))
    )
    (net (code "17") (name "LIMZ1") (class "Default")
      (node (ref "LIMZ") (pin "1") (pinfunction "1_1") (pintype "passive"))
      (node (ref "MCU") (pin "47") (pinfunction "PF1_47") (pintype "bidirectional"))
    )
    (net (code "18") (name "LIMZ2") (class "Default")
      (node (ref "LIMZ") (pin "4") (pinfunction "1_4") (pintype "passive"))
      (node (ref "MCU") (pin "48") (pinfunction "PF2_48") (pintype "bidirectional"))
    )
    (net (code "19") (name "MDXD") (class "Default")
      (node (ref "MDX") (pin "3") (pinfunction "1_3") (pintype "passive"))
      (node (ref "R14") (pin "2") (pinfunction "2_2") (pintype "passive"))
    )
    (net (code "20") (name "MDXE") (class "Default")
      (node (ref "MDX") (pin "4") (pinfunction "1_4") (pintype "passive"))
      (node (ref "R17") (pin "2") (pinfunction "2_2") (pintype "passive"))
    )
    (net (code "21") (name "MDYD") (class "Default")
      (node (ref "MDY") (pin "3") (pinfunction "1_3") (pintype "passive"))
      (node (ref "R18") (pin "2") (pinfunction "2_2") (pintype "passive"))
    )
    (net (code "22") (name "MDYE") (class "Default")
      (node (ref "MDY") (pin "4") (pinfunction "1_4") (pintype "passive"))
      (node (ref "R19") (pin "2") (pinfunction "2_2") (pintype "passive"))
    )
    (net (code "23") (name "MDZD") (class "Default")
      (node (ref "MDZ") (pin "3") (pinfunction "1_3") (pintype "passive"))
      (node (ref "R20") (pin "2") (pinfunction "2_2") (pintype "passive"))
    )
    (net (code "24") (name "MDZE") (class "Default")
      (node (ref "MDZ") (pin "4") (pinfunction "1_4") (pintype "passive"))
      (node (ref "R21") (pin "2") (pinfunction "2_2") (pintype "passive"))
    )
    (net (code "25") (name "MISO") (class "Default")
      (node (ref "BOUT") (pin "5") (pinfunction "1_5") (pintype "passive"))
      (node (ref "IC10") (pin "7") (pinfunction "DO_7") (pintype "output"))
      (node (ref "IC11") (pin "7") (pinfunction "DO_7") (pintype "output"))
      (node (ref "IC12") (pin "7") (pinfunction "DO_7") (pintype "output"))
      (node (ref "IC13") (pin "7") (pinfunction "DO_7") (pintype "output"))
      (node (ref "IC3") (pin "7") (pinfunction "DO_7") (pintype "output"))
      (node (ref "IC5") (pin "7") (pinfunction "DO_7") (pintype "output"))
      (node (ref "IC6") (pin "7") (pinfunction "DO_7") (pintype "output"))
      (node (ref "IC7") (pin "7") (pinfunction "DO_7") (pintype "output"))
      (node (ref "IC8") (pin "7") (pinfunction "DO_7") (pintype "output"))
      (node (ref "IC9") (pin "7") (pinfunction "DO_7") (pintype "output"))
      (node (ref "MCU") (pin "32") (pinfunction "PD6_32") (pintype "bidirectional"))
    )
    (net (code "26") (name "Net-(C16-P$1)") (class "Default")
      (node (ref "C16") (pin "1") (pinfunction "P$1_1") (pintype "passive"))
      (node (ref "FB1") (pin "2") (pinfunction "P$2_2") (pintype "passive"))
      (node (ref "IC5") (pin "2") (pinfunction "T-_2") (pintype "input"))
    )
    (net (code "27") (name "Net-(C16-P$2)") (class "Default")
      (node (ref "C16") (pin "2") (pinfunction "P$2_2") (pintype "passive"))
      (node (ref "FB2") (pin "2") (pinfunction "P$2_2") (pintype "passive"))
      (node (ref "IC5") (pin "3") (pinfunction "T+_3") (pintype "input"))
    )
    (net (code "28") (name "Net-(C17-P$1)") (class "Default")
      (node (ref "C17") (pin "1") (pinfunction "P$1_1") (pintype "passive"))
      (node (ref "FB3") (pin "2") (pinfunction "P$2_2") (pintype "passive"))
      (node (ref "IC6") (pin "2") (pinfunction "T-_2") (pintype "input"))
    )
    (net (code "29") (name "Net-(C17-P$2)") (class "Default")
      (node (ref "C17") (pin "2") (pinfunction "P$2_2") (pintype "passive"))
      (node (ref "FB4") (pin "2") (pinfunction "P$2_2") (pintype "passive"))
      (node (ref "IC6") (pin "3") (pinfunction "T+_3") (pintype "input"))
    )
    (net (code "30") (name "Net-(C18-P$1)") (class "Default")
      (node (ref "C18") (pin "1") (pinfunction "P$1_1") (pintype "passive"))
      (node (ref "FB5") (pin "2") (pinfunction "P$2_2") (pintype "passive"))
      (node (ref "IC7") (pin "2") (pinfunction "T-_2") (pintype "input"))
    )
    (net (code "31") (name "Net-(C18-P$2)") (class "Default")
      (node (ref "C18") (pin "2") (pinfunction "P$2_2") (pintype "passive"))
      (node (ref "FB6") (pin "2") (pinfunction "P$2_2") (pintype "passive"))
      (node (ref "IC7") (pin "3") (pinfunction "T+_3") (pintype "input"))
    )
    (net (code "32") (name "Net-(C19-P$1)") (class "Default")
      (node (ref "C19") (pin "1") (pinfunction "P$1_1") (pintype "passive"))
      (node (ref "FB7") (pin "2") (pinfunction "P$2_2") (pintype "passive"))
      (node (ref "IC8") (pin "2") (pinfunction "T-_2") (pintype "input"))
    )
    (net (code "33") (name "Net-(C19-P$2)") (class "Default")
      (node (ref "C19") (pin "2") (pinfunction "P$2_2") (pintype "passive"))
      (node (ref "FB8") (pin "2") (pinfunction "P$2_2") (pintype "passive"))
      (node (ref "IC8") (pin "3") (pinfunction "T+_3") (pintype "input"))
    )
    (net (code "34") (name "Net-(C20-P$1)") (class "Default")
      (node (ref "C20") (pin "1") (pinfunction "P$1_1") (pintype "passive"))
      (node (ref "FB9") (pin "2") (pinfunction "P$2_2") (pintype "passive"))
      (node (ref "IC9") (pin "2") (pinfunction "T-_2") (pintype "input"))
    )
    (net (code "35") (name "Net-(C20-P$2)") (class "Default")
      (node (ref "C20") (pin "2") (pinfunction "P$2_2") (pintype "passive"))
      (node (ref "FB10") (pin "2") (pinfunction "P$2_2") (pintype "passive"))
      (node (ref "IC9") (pin "3") (pinfunction "T+_3") (pintype "input"))
    )
    (net (code "36") (name "Net-(C26-P$1)") (class "Default")
      (node (ref "C26") (pin "1") (pinfunction "P$1_1") (pintype "passive"))
      (node (ref "FB11") (pin "2") (pinfunction "P$2_2") (pintype "passive"))
      (node (ref "IC10") (pin "2") (pinfunction "T-_2") (pintype "input"))
    )
    (net (code "37") (name "Net-(C26-P$2)") (class "Default")
      (node (ref "C26") (pin "2") (pinfunction "P$2_2") (pintype "passive"))
      (node (ref "FB12") (pin "2") (pinfunction "P$2_2") (pintype "passive"))
      (node (ref "IC10") (pin "3") (pinfunction "T+_3") (pintype "input"))
    )
    (net (code "38") (name "Net-(C27-P$1)") (class "Default")
      (node (ref "C27") (pin "1") (pinfunction "P$1_1") (pintype "passive"))
      (node (ref "FB13") (pin "2") (pinfunction "P$2_2") (pintype "passive"))
      (node (ref "IC11") (pin "2") (pinfunction "T-_2") (pintype "input"))
    )
    (net (code "39") (name "Net-(C27-P$2)") (class "Default")
      (node (ref "C27") (pin "2") (pinfunction "P$2_2") (pintype "passive"))
      (node (ref "FB14") (pin "2") (pinfunction "P$2_2") (pintype "passive"))
      (node (ref "IC11") (pin "3") (pinfunction "T+_3") (pintype "input"))
    )
    (net (code "40") (name "Net-(C28-P$1)") (class "Default")
      (node (ref "C28") (pin "1") (pinfunction "P$1_1") (pintype "passive"))
      (node (ref "FB15") (pin "2") (pinfunction "P$2_2") (pintype "passive"))
      (node (ref "IC12") (pin "2") (pinfunction "T-_2") (pintype "input"))
    )
    (net (code "41") (name "Net-(C28-P$2)") (class "Default")
      (node (ref "C28") (pin "2") (pinfunction "P$2_2") (pintype "passive"))
      (node (ref "FB16") (pin "2") (pinfunction "P$2_2") (pintype "passive"))
      (node (ref "IC12") (pin "3") (pinfunction "T+_3") (pintype "input"))
    )
    (net (code "42") (name "Net-(C29-P$1)") (class "Default")
      (node (ref "C29") (pin "1") (pinfunction "P$1_1") (pintype "passive"))
      (node (ref "FB17") (pin "2") (pinfunction "P$2_2") (pintype "passive"))
      (node (ref "IC13") (pin "2") (pinfunction "T-_2") (pintype "input"))
    )
    (net (code "43") (name "Net-(C29-P$2)") (class "Default")
      (node (ref "C29") (pin "2") (pinfunction "P$2_2") (pintype "passive"))
      (node (ref "FB18") (pin "2") (pinfunction "P$2_2") (pintype "passive"))
      (node (ref "IC13") (pin "3") (pinfunction "T+_3") (pintype "input"))
    )
    (net (code "44") (name "Net-(C35-P$1)") (class "Default")
      (node (ref "C35") (pin "1") (pinfunction "P$1_1") (pintype "passive"))
      (node (ref "FB19") (pin "2") (pinfunction "P$2_2") (pintype "passive"))
      (node (ref "IC3") (pin "2") (pinfunction "T-_2") (pintype "input"))
    )
    (net (code "45") (name "Net-(C35-P$2)") (class "Default")
      (node (ref "C35") (pin "2") (pinfunction "P$2_2") (pintype "passive"))
      (node (ref "FB20") (pin "2") (pinfunction "P$2_2") (pintype "passive"))
      (node (ref "IC3") (pin "3") (pinfunction "T+_3") (pintype "input"))
    )
    (net (code "46") (name "Net-(IC1A-OUT)") (class "Default")
      (node (ref "C7") (pin "+") (pinfunction "+_+") (pintype "passive"))
      (node (ref "IC1") (pin "3") (pinfunction "OUT_3") (pintype "output"))
      (node (ref "L1") (pin "1") (pinfunction "1_1") (pintype "passive"))
    )
    (net (code "47") (name "Net-(IC4-3V3OUT)") (class "Default")
      (node (ref "C36") (pin "1") (pinfunction "1_1") (pintype "passive"))
      (node (ref "IC4") (pin "17") (pinfunction "3V3OUT_17") (pintype "output"))
      (node (ref "IC4") (pin "4") (pinfunction "VCCIO_4") (pintype "power_in"))
    )
    (net (code "48") (name "Net-(IC4-RXLED)") (class "Default")
      (node (ref "IC4") (pin "22") (pinfunction "RXLED_22") (pintype "input"))
      (node (ref "LED2G") (pin "C") (pinfunction "C_C") (pintype "passive"))
    )
    (net (code "49") (name "Net-(IC4-TXLED)") (class "Default")
      (node (ref "IC4") (pin "23") (pinfunction "TXLED_23") (pintype "input"))
      (node (ref "LED1R") (pin "C") (pinfunction "C_C") (pintype "passive"))
    )
    (net (code "50") (name "Net-(LED1R-PadA)") (class "Default")
      (node (ref "LED1R") (pin "A") (pinfunction "A_A") (pintype "passive"))
      (node (ref "R15") (pin "2") (pinfunction "2_2") (pintype "passive"))
    )
    (net (code "51") (name "Net-(LED2G-PadA)") (class "Default")
      (node (ref "LED2G") (pin "A") (pinfunction "A_A") (pintype "passive"))
      (node (ref "R16") (pin "2") (pinfunction "2_2") (pintype "passive"))
    )
    (net (code "52") (name "Net-(MCU-PDI)") (class "Default")
      (node (ref "MCU") (pin "56") (pinfunction "PDI_56") (pintype "bidirectional"))
      (node (ref "PDI") (pin "1") (pinfunction "1_1") (pintype "passive"))
    )
    (net (code "53") (name "Net-(MCU-PR0)") (class "Default")
      (node (ref "C12") (pin "1") (pinfunction "1_1") (pintype "passive"))
      (node (ref "MCU") (pin "58") (pinfunction "PR0_58") (pintype "bidirectional"))
      (node (ref "Q10") (pin "2") (pinfunction "2_2") (pintype "passive"))
    )
    (net (code "54") (name "Net-(MCU-PR1)") (class "Default")
      (node (ref "C13") (pin "1") (pinfunction "1_1") (pintype "passive"))
      (node (ref "MCU") (pin "59") (pinfunction "PR1_59") (pintype "bidirectional"))
      (node (ref "Q10") (pin "1") (pinfunction "1_1") (pintype "passive"))
    )
    (net (code "55") (name "Net-(Q1-D)") (class "Default")
      (node (ref "Q1") (pin "3") (pinfunction "D_3") (pintype "passive"))
      (node (ref "R11") (pin "1") (pinfunction "1_1") (pintype "passive"))
    )
    (net (code "56") (name "Net-(Q2-D)") (class "Default")
      (node (ref "Q2") (pin "3") (pinfunction "D_3") (pintype "passive"))
      (node (ref "R12") (pin "1") (pinfunction "1_1") (pintype "passive"))
    )
    (net (code "57") (name "Net-(Q3-D)") (class "Default")
      (node (ref "Q3") (pin "3") (pinfunction "D_3") (pintype "passive"))
      (node (ref "R13") (pin "1") (pinfunction "1_1") (pintype "passive"))
    )
    (net (code "58") (name "Net-(Q4-D)") (class "Default")
      (node (ref "Q4") (pin "3") (pinfunction "D_3") (pintype "passive"))
      (node (ref "R14") (pin "1") (pinfunction "1_1") (pintype "passive"))
    )
    (net (code "59") (name "Net-(Q5-D)") (class "Default")
      (node (ref "Q5") (pin "3") (pinfunction "D_3") (pintype "passive"))
      (node (ref "R17") (pin "1") (pinfunction "1_1") (pintype "passive"))
    )
    (net (code "60") (name "Net-(Q6-D)") (class "Default")
      (node (ref "Q6") (pin "3") (pinfunction "D_3") (pintype "passive"))
      (node (ref "R18") (pin "1") (pinfunction "1_1") (pintype "passive"))
    )
    (net (code "61") (name "Net-(Q7-D)") (class "Default")
      (node (ref "Q7") (pin "3") (pinfunction "D_3") (pintype "passive"))
      (node (ref "R19") (pin "1") (pinfunction "1_1") (pintype "passive"))
    )
    (net (code "62") (name "Net-(Q8-D)") (class "Default")
      (node (ref "Q8") (pin "3") (pinfunction "D_3") (pintype "passive"))
      (node (ref "R20") (pin "1") (pinfunction "1_1") (pintype "passive"))
    )
    (net (code "63") (name "Net-(Q9-D)") (class "Default")
      (node (ref "Q9") (pin "3") (pinfunction "D_3") (pintype "passive"))
      (node (ref "R21") (pin "1") (pinfunction "1_1") (pintype "passive"))
    )
    (net (code "64") (name "Net-(RESET-S)") (class "Default")
      (node (ref "R10") (pin "2") (pinfunction "2_2") (pintype "passive"))
      (node (ref "RESET") (pin "1") (pinfunction "S_1") (pintype "passive"))
    )
    (net (code "65") (name "PA2") (class "Default")
      (node (ref "MCU") (pin "64") (pinfunction "PA2_64") (pintype "bidirectional"))
      (node (ref "Q5") (pin "1") (pinfunction "G_1") (pintype "passive"))
      (node (ref "R5") (pin "1") (pinfunction "1_1") (pintype "passive"))
    )
    (net (code "66") (name "PA3") (class "Default")
      (node (ref "MCU") (pin "1") (pinfunction "PA3_1") (pintype "bidirectional"))
      (node (ref "Q4") (pin "1") (pinfunction "G_1") (pintype "passive"))
      (node (ref "R4") (pin "1") (pinfunction "1_1") (pintype "passive"))
    )
    (net (code "67") (name "PA4") (class "Default")
      (node (ref "MCU") (pin "2") (pinfunction "PA4_2") (pintype "bidirectional"))
      (node (ref "Q7") (pin "1") (pinfunction "G_1") (pintype "passive"))
      (node (ref "R7") (pin "1") (pinfunction "1_1") (pintype "passive"))
    )
    (net (code "68") (name "PA5") (class "Default")
      (node (ref "MCU") (pin "3") (pinfunction "PA5_3") (pintype "bidirectional"))
      (node (ref "Q6") (pin "1") (pinfunction "G_1") (pintype "passive"))
      (node (ref "R6") (pin "1") (pinfunction "1_1") (pintype "passive"))
    )
    (net (code "69") (name "PA6") (class "Default")
      (node (ref "MCU") (pin "4") (pinfunction "PA6_4") (pintype "bidirectional"))
      (node (ref "Q9") (pin "1") (pinfunction "G_1") (pintype "passive"))
      (node (ref "R9") (pin "1") (pinfunction "1_1") (pintype "passive"))
    )
    (net (code "70") (name "PA7") (class "Default")
      (node (ref "MCU") (pin "5") (pinfunction "PA7_5") (pintype "bidirectional"))
      (node (ref "Q8") (pin "1") (pinfunction "G_1") (pintype "passive"))
      (node (ref "R8") (pin "1") (pinfunction "1_1") (pintype "passive"))
    )
    (net (code "71") (name "PB0") (class "Default")
      (node (ref "BEAD2") (pin "2") (pinfunction "2_2") (pintype "passive"))
      (node (ref "C38") (pin "1") (pinfunction "1_1") (pintype "passive"))
      (node (ref "MCU") (pin "6") (pinfunction "PB0_6") (pintype "bidirectional"))
    )
    (net (code "72") (name "PB4") (class "Default")
      (node (ref "BEAD1") (pin "2") (pinfunction "2_2") (pintype "passive"))
      (node (ref "C37") (pin "1") (pinfunction "1_1") (pintype "passive"))
      (node (ref "MCU") (pin "10") (pinfunction "PB4_10") (pintype "bidirectional"))
    )
    (net (code "73") (name "PC0") (class "Default")
      (node (ref "MCU") (pin "16") (pinfunction "PC0_16") (pintype "bidirectional"))
      (node (ref "Q3") (pin "1") (pinfunction "G_1") (pintype "passive"))
      (node (ref "R3") (pin "1") (pinfunction "1_1") (pintype "passive"))
    )
    (net (code "74") (name "PC1") (class "Default")
      (node (ref "IC5") (pin "6") (pinfunction "/CS_6") (pintype "input"))
      (node (ref "MCU") (pin "17") (pinfunction "PC1_17") (pintype "bidirectional"))
    )
    (net (code "75") (name "PC2") (class "Default")
      (node (ref "IC6") (pin "6") (pinfunction "/CS_6") (pintype "input"))
      (node (ref "MCU") (pin "18") (pinfunction "PC2_18") (pintype "bidirectional"))
    )
    (net (code "76") (name "PC3") (class "Default")
      (node (ref "IC7") (pin "6") (pinfunction "/CS_6") (pintype "input"))
      (node (ref "MCU") (pin "19") (pinfunction "PC3_19") (pintype "bidirectional"))
    )
    (net (code "77") (name "PC4") (class "Default")
      (node (ref "IC8") (pin "6") (pinfunction "/CS_6") (pintype "input"))
      (node (ref "MCU") (pin "20") (pinfunction "PC4_20") (pintype "bidirectional"))
    )
    (net (code "78") (name "PC5") (class "Default")
      (node (ref "IC9") (pin "6") (pinfunction "/CS_6") (pintype "input"))
      (node (ref "MCU") (pin "21") (pinfunction "PC5_21") (pintype "bidirectional"))
    )
    (net (code "79") (name "PC6") (class "Default")
      (node (ref "IC10") (pin "6") (pinfunction "/CS_6") (pintype "input"))
      (node (ref "MCU") (pin "22") (pinfunction "PC6_22") (pintype "bidirectional"))
    )
    (net (code "80") (name "PC7") (class "Default")
      (node (ref "IC11") (pin "6") (pinfunction "/CS_6") (pintype "input"))
      (node (ref "MCU") (pin "23") (pinfunction "PC7_23") (pintype "bidirectional"))
    )
    (net (code "81") (name "PD0") (class "Default")
      (node (ref "IC12") (pin "6") (pinfunction "/CS_6") (pintype "input"))
      (node (ref "MCU") (pin "26") (pinfunction "PD0_26") (pintype "bidirectional"))
    )
    (net (code "82") (name "PD1") (class "Default")
      (node (ref "IC13") (pin "6") (pinfunction "/CS_6") (pintype "input"))
      (node (ref "MCU") (pin "27") (pinfunction "PD1_27") (pintype "bidirectional"))
    )
    (net (code "83") (name "PD2") (class "Default")
      (node (ref "IC3") (pin "6") (pinfunction "/CS_6") (pintype "input"))
      (node (ref "MCU") (pin "28") (pinfunction "PD2_28") (pintype "bidirectional"))
    )
    (net (code "84") (name "PD3") (class "Default")
      (node (ref "MCU") (pin "29") (pinfunction "PD3_29") (pintype "bidirectional"))
      (node (ref "Q2") (pin "1") (pinfunction "G_1") (pintype "passive"))
      (node (ref "R2") (pin "1") (pinfunction "1_1") (pintype "passive"))
    )
    (net (code "85") (name "PD4") (class "Default")
      (node (ref "MCU") (pin "30") (pinfunction "PD4_30") (pintype "bidirectional"))
      (node (ref "Q1") (pin "1") (pinfunction "G_1") (pintype "passive"))
      (node (ref "R1") (pin "1") (pinfunction "1_1") (pintype "passive"))
    )
    (net (code "86") (name "PD5") (class "Default")
      (node (ref "BOUT") (pin "4") (pinfunction "1_4") (pintype "passive"))
      (node (ref "MCU") (pin "31") (pinfunction "PD5_31") (pintype "bidirectional"))
    )
    (net (code "87") (name "PUL1") (class "Default")
      (node (ref "MDX") (pin "2") (pinfunction "1_2") (pintype "passive"))
      (node (ref "R11") (pin "2") (pinfunction "2_2") (pintype "passive"))
    )
    (net (code "88") (name "PUL2") (class "Default")
      (node (ref "MDY") (pin "2") (pinfunction "1_2") (pintype "passive"))
      (node (ref "R12") (pin "2") (pinfunction "2_2") (pintype "passive"))
    )
    (net (code "89") (name "PUL3") (class "Default")
      (node (ref "MDZ") (pin "2") (pinfunction "1_2") (pintype "passive"))
      (node (ref "R13") (pin "2") (pinfunction "2_2") (pintype "passive"))
    )
    (net (code "90") (name "RXD") (class "Default")
      (node (ref "IC4") (pin "5") (pinfunction "RXD_5") (pintype "input"))
      (node (ref "MCU") (pin "39") (pinfunction "PE3_39") (pintype "bidirectional"))
    )
    (net (code "91") (name "T1+") (class "Default")
      (node (ref "FB2") (pin "1") (pinfunction "P$1_1") (pintype "passive"))
      (node (ref "T1") (pin "2") (pinfunction "1_2") (pintype "passive"))
    )
    (net (code "92") (name "T1-") (class "Default")
      (node (ref "FB1") (pin "1") (pinfunction "P$1_1") (pintype "passive"))
      (node (ref "T1") (pin "1") (pinfunction "1_1") (pintype "passive"))
    )
    (net (code "93") (name "T2+") (class "Default")
      (node (ref "FB4") (pin "1") (pinfunction "P$1_1") (pintype "passive"))
      (node (ref "T1") (pin "4") (pinfunction "1_4") (pintype "passive"))
    )
    (net (code "94") (name "T2-") (class "Default")
      (node (ref "FB3") (pin "1") (pinfunction "P$1_1") (pintype "passive"))
      (node (ref "T1") (pin "3") (pinfunction "1_3") (pintype "passive"))
    )
    (net (code "95") (name "T3+") (class "Default")
      (node (ref "FB6") (pin "1") (pinfunction "P$1_1") (pintype "passive"))
      (node (ref "T1") (pin "6") (pinfunction "1_6") (pintype "passive"))
    )
    (net (code "96") (name "T3-") (class "Default")
      (node (ref "FB5") (pin "1") (pinfunction "P$1_1") (pintype "passive"))
      (node (ref "T1") (pin "5") (pinfunction "1_5") (pintype "passive"))
    )
    (net (code "97") (name "T4+") (class "Default")
      (node (ref "FB8") (pin "1") (pinfunction "P$1_1") (pintype "passive"))
      (node (ref "T1") (pin "8") (pinfunction "1_8") (pintype "passive"))
    )
    (net (code "98") (name "T4-") (class "Default")
      (node (ref "FB7") (pin "1") (pinfunction "P$1_1") (pintype "passive"))
      (node (ref "T1") (pin "7") (pinfunction "1_7") (pintype "passive"))
    )
    (net (code "99") (name "T5+") (class "Default")
      (node (ref "FB10") (pin "1") (pinfunction "P$1_1") (pintype "passive"))
      (node (ref "T1") (pin "10") (pinfunction "1_10") (pintype "passive"))
    )
    (net (code "100") (name "T5-") (class "Default")
      (node (ref "FB9") (pin "1") (pinfunction "P$1_1") (pintype "passive"))
      (node (ref "T1") (pin "9") (pinfunction "1_9") (pintype "passive"))
    )
    (net (code "101") (name "T6+") (class "Default")
      (node (ref "FB12") (pin "1") (pinfunction "P$1_1") (pintype "passive"))
      (node (ref "T2") (pin "2") (pinfunction "1_2") (pintype "passive"))
    )
    (net (code "102") (name "T6-") (class "Default")
      (node (ref "FB11") (pin "1") (pinfunction "P$1_1") (pintype "passive"))
      (node (ref "T2") (pin "1") (pinfunction "1_1") (pintype "passive"))
    )
    (net (code "103") (name "T7+") (class "Default")
      (node (ref "FB14") (pin "1") (pinfunction "P$1_1") (pintype "passive"))
      (node (ref "T2") (pin "4") (pinfunction "1_4") (pintype "passive"))
    )
    (net (code "104") (name "T7-") (class "Default")
      (node (ref "FB13") (pin "1") (pinfunction "P$1_1") (pintype "passive"))
      (node (ref "T2") (pin "3") (pinfunction "1_3") (pintype "passive"))
    )
    (net (code "105") (name "T8+") (class "Default")
      (node (ref "FB16") (pin "1") (pinfunction "P$1_1") (pintype "passive"))
      (node (ref "T2") (pin "6") (pinfunction "1_6") (pintype "passive"))
    )
    (net (code "106") (name "T8-") (class "Default")
      (node (ref "FB15") (pin "1") (pinfunction "P$1_1") (pintype "passive"))
      (node (ref "T2") (pin "5") (pinfunction "1_5") (pintype "passive"))
    )
    (net (code "107") (name "T9+") (class "Default")
      (node (ref "FB18") (pin "1") (pinfunction "P$1_1") (pintype "passive"))
      (node (ref "T2") (pin "8") (pinfunction "1_8") (pintype "passive"))
    )
    (net (code "108") (name "T9-") (class "Default")
      (node (ref "FB17") (pin "1") (pinfunction "P$1_1") (pintype "passive"))
      (node (ref "T2") (pin "7") (pinfunction "1_7") (pintype "passive"))
    )
    (net (code "109") (name "T10+") (class "Default")
      (node (ref "FB20") (pin "1") (pinfunction "P$1_1") (pintype "passive"))
      (node (ref "T2") (pin "10") (pinfunction "1_10") (pintype "passive"))
    )
    (net (code "110") (name "T10-") (class "Default")
      (node (ref "FB19") (pin "1") (pinfunction "P$1_1") (pintype "passive"))
      (node (ref "T2") (pin "9") (pinfunction "1_9") (pintype "passive"))
    )
    (net (code "111") (name "TXD") (class "Default")
      (node (ref "IC4") (pin "1") (pinfunction "TXD_1") (pintype "output"))
      (node (ref "MCU") (pin "38") (pinfunction "PE2_38") (pintype "bidirectional"))
    )
    (net (code "112") (name "VCC") (class "Default")
      (node (ref "LIMX") (pin "3") (pinfunction "1_3") (pintype "passive"))
      (node (ref "LIMX") (pin "6") (pinfunction "1_6") (pintype "passive"))
      (node (ref "LIMY") (pin "3") (pinfunction "1_3") (pintype "passive"))
      (node (ref "LIMY") (pin "6") (pinfunction "1_6") (pintype "passive"))
      (node (ref "LIMZ") (pin "3") (pinfunction "1_3") (pintype "passive"))
      (node (ref "LIMZ") (pin "6") (pinfunction "1_6") (pintype "passive"))
    )
    (net (code "113") (name "unconnected-(IC4-CTS-Pad11)") (class "Default")
      (node (ref "IC4") (pin "11") (pinfunction "CTS_11") (pintype "input"))
    )
    (net (code "114") (name "unconnected-(IC4-DCD-Pad10)") (class "Default")
      (node (ref "IC4") (pin "10") (pinfunction "DCD_10") (pintype "input"))
    )
    (net (code "115") (name "unconnected-(IC4-DSR-Pad9)") (class "Default")
      (node (ref "IC4") (pin "9") (pinfunction "DSR_9") (pintype "input"))
    )
    (net (code "116") (name "unconnected-(IC4-DTR-Pad2)") (class "Default")
      (node (ref "IC4") (pin "2") (pinfunction "DTR_2") (pintype "output"))
    )
    (net (code "117") (name "unconnected-(IC4-OSCI-Pad27)") (class "Default")
      (node (ref "IC4") (pin "27") (pinfunction "OSCI_27") (pintype "input"))
    )
    (net (code "118") (name "unconnected-(IC4-OSCO-Pad28)") (class "Default")
      (node (ref "IC4") (pin "28") (pinfunction "OSCO_28") (pintype "output"))
    )
    (net (code "119") (name "unconnected-(IC4-PWREN-Pad14)") (class "Default")
      (node (ref "IC4") (pin "14") (pinfunction "PWREN_14") (pintype "input"))
    )
    (net (code "120") (name "unconnected-(IC4-RESET-Pad19)") (class "Default")
      (node (ref "IC4") (pin "19") (pinfunction "RESET_19") (pintype "input"))
    )
    (net (code "121") (name "unconnected-(IC4-RI-Pad6)") (class "Default")
      (node (ref "IC4") (pin "6") (pinfunction "RI_6") (pintype "input"))
    )
    (net (code "122") (name "unconnected-(IC4-RTS-Pad3)") (class "Default")
      (node (ref "IC4") (pin "3") (pinfunction "RTS_3") (pintype "output"))
    )
    (net (code "123") (name "unconnected-(IC4-SLEEP-Pad12)") (class "Default")
      (node (ref "IC4") (pin "12") (pinfunction "SLEEP_12") (pintype "input"))
    )
    (net (code "124") (name "unconnected-(IC4-TXDEN-Pad13)") (class "Default")
      (node (ref "IC4") (pin "13") (pinfunction "TXDEN_13") (pintype "input"))
    )
    (net (code "125") (name "unconnected-(MCU-PB1-Pad7)") (class "Default")
      (node (ref "MCU") (pin "7") (pinfunction "PB1_7") (pintype "bidirectional"))
    )
    (net (code "126") (name "unconnected-(MCU-PB2-Pad8)") (class "Default")
      (node (ref "MCU") (pin "8") (pinfunction "PB2_8") (pintype "bidirectional"))
    )
    (net (code "127") (name "unconnected-(MCU-PB3-Pad9)") (class "Default")
      (node (ref "MCU") (pin "9") (pinfunction "PB3_9") (pintype "bidirectional"))
    )
    (net (code "128") (name "unconnected-(MCU-PB5-Pad11)") (class "Default")
      (node (ref "MCU") (pin "11") (pinfunction "PB5_11") (pintype "bidirectional"))
    )
    (net (code "129") (name "unconnected-(MCU-PB6-Pad12)") (class "Default")
      (node (ref "MCU") (pin "12") (pinfunction "PB6_12") (pintype "bidirectional"))
    )
    (net (code "130") (name "unconnected-(MCU-PB7-Pad13)") (class "Default")
      (node (ref "MCU") (pin "13") (pinfunction "PB7_13") (pintype "bidirectional"))
    )
    (net (code "131") (name "unconnected-(MCU-PE0-Pad36)") (class "Default")
      (node (ref "MCU") (pin "36") (pinfunction "PE0_36") (pintype "bidirectional"))
    )
    (net (code "132") (name "unconnected-(MCU-PE1-Pad37)") (class "Default")
      (node (ref "MCU") (pin "37") (pinfunction "PE1_37") (pintype "bidirectional"))
    )
    (net (code "133") (name "unconnected-(MCU-PE6-Pad42)") (class "Default")
      (node (ref "MCU") (pin "42") (pinfunction "PE6_42") (pintype "bidirectional"))
    )
    (net (code "134") (name "unconnected-(MCU-PE7-Pad43)") (class "Default")
      (node (ref "MCU") (pin "43") (pinfunction "PE7_43") (pintype "bidirectional"))
    )
    (net (code "135") (name "unconnected-(MCU-PF0-Pad46)") (class "Default")
      (node (ref "MCU") (pin "46") (pinfunction "PF0_46") (pintype "bidirectional"))
    )
    (net (code "136") (name "unconnected-(MCU-PF3-Pad49)") (class "Default")
      (node (ref "MCU") (pin "49") (pinfunction "PF3_49") (pintype "bidirectional"))
    )
    (net (code "137") (name "unconnected-(MCU-PF4-Pad50)") (class "Default")
      (node (ref "MCU") (pin "50") (pinfunction "PF4_50") (pintype "bidirectional"))
    )
    (net (code "138") (name "unconnected-(MCU-PF5-Pad51)") (class "Default")
      (node (ref "MCU") (pin "51") (pinfunction "PF5_51") (pintype "bidirectional"))
    )
    (net (code "139") (name "unconnected-(MCU-PF6-Pad54)") (class "Default")
      (node (ref "MCU") (pin "54") (pinfunction "PF6_54") (pintype "bidirectional"))
    )
    (net (code "140") (name "unconnected-(MCU-PF7-Pad55)") (class "Default")
      (node (ref "MCU") (pin "55") (pinfunction "PF7_55") (pintype "bidirectional"))
    )
    (net (code "141") (name "unconnected-(PDI-Pad3)") (class "Default")
      (node (ref "PDI") (pin "3") (pinfunction "3_3") (pintype "passive"))
    )
    (net (code "142") (name "unconnected-(PDI-Pad4)") (class "Default")
      (node (ref "PDI") (pin "4") (pinfunction "4_4") (pintype "passive"))
    )
    (net (code "143") (name "unconnected-(USB-Pad4)") (class "Default")
      (node (ref "USB") (pin "4") (pinfunction "4_4") (pintype "input"))
    )
  )
)
